# S2C_IOs3V3.net
KiCad netlist of a schematic drawn in Altium Designer
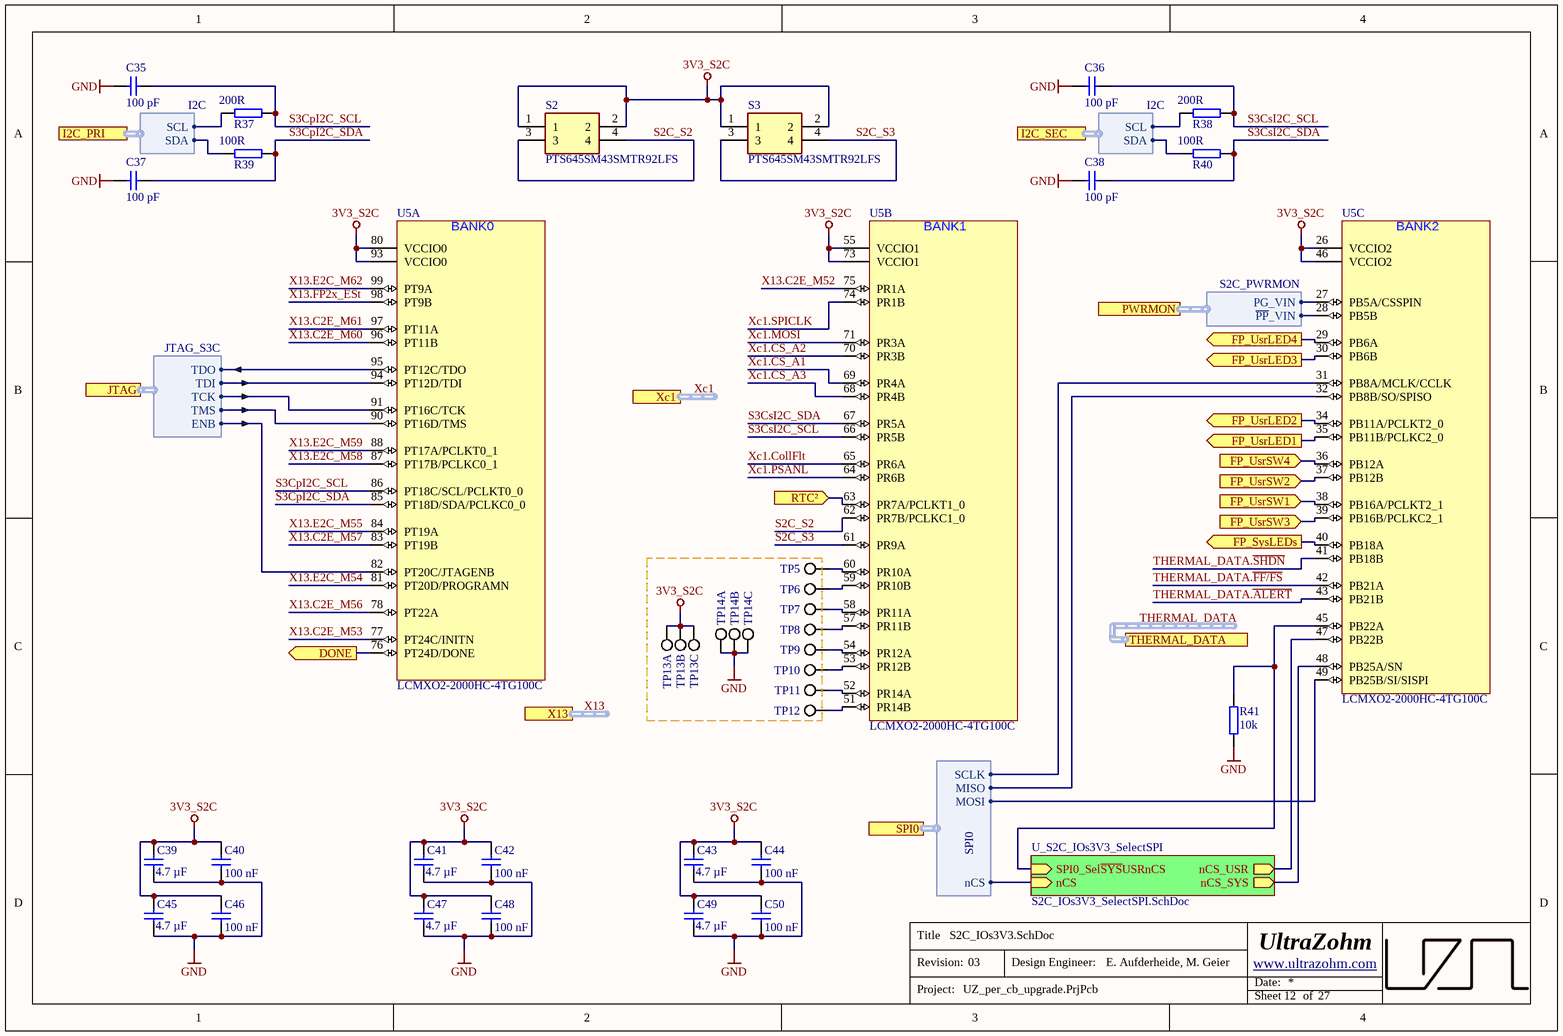
[diagram p0: S2C_IOs3V3.SchDoc]

(export (version "E")
  (design (tool "Eeschema 10.0.6"))
  (components
    (comp (ref "C35")
      (value "100 pF")
      (footprint "C_0603_TE")
      (description "Generic capacitor")
      (fields
        (field (name "MANUFACTURER PART NUMBER") "UZgen_C_0603_100pF_50V_X7R")
        (field (name "MANUFACTURER") "UZgen")
        (field (name "CREATED FROM") "UZgenTool")
      )
      (libsource (lib "user") (part "CAP-NP"))
    )
    (comp (ref "C36")
      (value "100 pF")
      (footprint "C_0603_TE")
      (description "Generic capacitor")
      (fields
        (field (name "MANUFACTURER PART NUMBER") "UZgen_C_0603_100pF_50V_X7R")
        (field (name "MANUFACTURER") "UZgen")
        (field (name "CREATED FROM") "UZgenTool")
      )
      (libsource (lib "user") (part "CAP-NP"))
    )
    (comp (ref "C37")
      (value "100 pF")
      (footprint "C_0603_TE")
      (description "Generic capacitor")
      (fields
        (field (name "MANUFACTURER PART NUMBER") "UZgen_C_0603_100pF_50V_X7R")
        (field (name "MANUFACTURER") "UZgen")
        (field (name "CREATED FROM") "UZgenTool")
      )
      (libsource (lib "user") (part "CAP-NP"))
    )
    (comp (ref "C38")
      (value "100 pF")
      (footprint "C_0603_TE")
      (description "Generic capacitor")
      (fields
        (field (name "MANUFACTURER PART NUMBER") "UZgen_C_0603_100pF_50V_X7R")
        (field (name "MANUFACTURER") "UZgen")
        (field (name "CREATED FROM") "UZgenTool")
      )
      (libsource (lib "user") (part "CAP-NP"))
    )
    (comp (ref "C39")
      (value "4.7 µF")
      (footprint "C_0603_TE")
      (description "Generic capacitor")
      (fields
        (field (name "MANUFACTURER PART NUMBER") "UZgen_C_0603_4.7uF_16V_X5R")
        (field (name "MANUFACTURER") "UZgen")
        (field (name "CREATED FROM") "MGeier")
      )
      (libsource (lib "user") (part "CAP-NP"))
    )
    (comp (ref "C40")
      (value "100 nF")
      (footprint "C_0603_TE")
      (description "Generic capacitor")
      (fields
        (field (name "TOLERANCE") "10 %")
        (field (name "VOLTAGE") "50 V")
        (field (name "CREATED FROM") "AGeiger")
      )
      (libsource (lib "user") (part "CAP-NP"))
    )
    (comp (ref "C41")
      (value "4.7 µF")
      (footprint "C_0603_TE")
      (description "Generic capacitor")
      (fields
        (field (name "MANUFACTURER PART NUMBER") "UZgen_C_0603_4.7uF_16V_X5R")
        (field (name "MANUFACTURER") "UZgen")
        (field (name "CREATED FROM") "MGeier")
      )
      (libsource (lib "user") (part "CAP-NP"))
    )
    (comp (ref "C42")
      (value "100 nF")
      (footprint "C_0603_TE")
      (description "Generic capacitor")
      (fields
        (field (name "TOLERANCE") "10 %")
        (field (name "VOLTAGE") "50 V")
        (field (name "CREATED FROM") "AGeiger")
      )
      (libsource (lib "user") (part "CAP-NP"))
    )
    (comp (ref "C43")
      (value "4.7 µF")
      (footprint "C_0603_TE")
      (description "Generic capacitor")
      (fields
        (field (name "MANUFACTURER PART NUMBER") "UZgen_C_0603_4.7uF_16V_X5R")
        (field (name "MANUFACTURER") "UZgen")
        (field (name "CREATED FROM") "MGeier")
      )
      (libsource (lib "user") (part "CAP-NP"))
    )
    (comp (ref "C44")
      (value "100 nF")
      (footprint "C_0603_TE")
      (description "Generic capacitor")
      (fields
        (field (name "TOLERANCE") "10 %")
        (field (name "VOLTAGE") "50 V")
        (field (name "CREATED FROM") "AGeiger")
      )
      (libsource (lib "user") (part "CAP-NP"))
    )
    (comp (ref "C45")
      (value "4.7 µF")
      (footprint "C_0603_TE")
      (description "Generic capacitor")
      (fields
        (field (name "MANUFACTURER PART NUMBER") "UZgen_C_0603_4.7uF_16V_X5R")
        (field (name "MANUFACTURER") "UZgen")
        (field (name "CREATED FROM") "MGeier")
      )
      (libsource (lib "user") (part "CAP-NP"))
    )
    (comp (ref "C46")
      (value "100 nF")
      (footprint "C_0603_TE")
      (description "Generic capacitor")
      (fields
        (field (name "TOLERANCE") "10 %")
        (field (name "VOLTAGE") "50 V")
        (field (name "CREATED FROM") "AGeiger")
      )
      (libsource (lib "user") (part "CAP-NP"))
    )
    (comp (ref "C47")
      (value "4.7 µF")
      (footprint "C_0603_TE")
      (description "Generic capacitor")
      (fields
        (field (name "MANUFACTURER PART NUMBER") "UZgen_C_0603_4.7uF_16V_X5R")
        (field (name "MANUFACTURER") "UZgen")
        (field (name "CREATED FROM") "MGeier")
      )
      (libsource (lib "user") (part "CAP-NP"))
    )
    (comp (ref "C48")
      (value "100 nF")
      (footprint "C_0603_TE")
      (description "Generic capacitor")
      (fields
        (field (name "TOLERANCE") "10 %")
        (field (name "VOLTAGE") "50 V")
        (field (name "CREATED FROM") "AGeiger")
      )
      (libsource (lib "user") (part "CAP-NP"))
    )
    (comp (ref "C49")
      (value "4.7 µF")
      (footprint "C_0603_TE")
      (description "Generic capacitor")
      (fields
        (field (name "MANUFACTURER PART NUMBER") "UZgen_C_0603_4.7uF_16V_X5R")
        (field (name "MANUFACTURER") "UZgen")
        (field (name "CREATED FROM") "MGeier")
      )
      (libsource (lib "user") (part "CAP-NP"))
    )
    (comp (ref "C50")
      (value "100 nF")
      (footprint "C_0603_TE")
      (description "Generic capacitor")
      (fields
        (field (name "TOLERANCE") "10 %")
        (field (name "VOLTAGE") "50 V")
        (field (name "CREATED FROM") "AGeiger")
      )
      (libsource (lib "user") (part "CAP-NP"))
    )
    (comp (ref "R37")
      (value "200R")
      (footprint "R_0603_TE")
      (description "Generic resistor")
      (fields
        (field (name "MANUFACTURER PART NUMBER") "UZgen_R_0603_200R")
        (field (name "MANUFACTURER") "UZgen")
        (field (name "CREATED FROM") "UZgenTool")
      )
      (libsource (lib "user") (part "RES"))
    )
    (comp (ref "R38")
      (value "200R")
      (footprint "R_0603_TE")
      (description "Generic resistor")
      (fields
        (field (name "MANUFACTURER PART NUMBER") "UZgen_R_0603_200R")
        (field (name "MANUFACTURER") "UZgen")
        (field (name "CREATED FROM") "UZgenTool")
      )
      (libsource (lib "user") (part "RES"))
    )
    (comp (ref "R39")
      (value "100R")
      (footprint "R_0603_TE")
      (description "Generic resistor")
      (fields
        (field (name "MANUFACTURER PART NUMBER") "UZgen_R_0603_100R")
        (field (name "MANUFACTURER") "UZgen")
        (field (name "CREATED FROM") "UZgenTool")
      )
      (libsource (lib "user") (part "RES"))
    )
    (comp (ref "R40")
      (value "100R")
      (footprint "R_0603_TE")
      (description "Generic resistor")
      (fields
        (field (name "MANUFACTURER PART NUMBER") "UZgen_R_0603_100R")
        (field (name "MANUFACTURER") "UZgen")
        (field (name "CREATED FROM") "UZgenTool")
      )
      (libsource (lib "user") (part "RES"))
    )
    (comp (ref "R41")
      (value "10k")
      (footprint "R_0603_TE")
      (description "Generic resistor")
      (fields
        (field (name "MANUFACTURER PART NUMBER") "UZgen_R_0603_10k")
        (field (name "MANUFACTURER") "UZgen")
        (field (name "CREATED FROM") "AGeiger")
      )
      (libsource (lib "user") (part "RES"))
    )
    (comp (ref "S2")
      (value "PTS645SM43SMTR92LFS")
      (footprint "PTS645_SMT")
      (description "50mA SPST 160gf 12V SMD-4P,6x6mm Tactile Switches ROHS")
      (fields
        (field (name "MOUSER PART NUMBER") "611-PTS645SM43SMTR92")
        (field (name "MANUFACTURER") "C&K COMPONENTS")
        (field (name "CREATED FROM") "AGeiger")
      )
      (libsource (lib "user") (part "PTS645SM43SMTR92LFS"))
    )
    (comp (ref "S3")
      (value "PTS645SM43SMTR92LFS")
      (footprint "PTS645_SMT")
      (description "50mA SPST 160gf 12V SMD-4P,6x6mm Tactile Switches ROHS")
      (fields
        (field (name "MOUSER PART NUMBER") "611-PTS645SM43SMTR92")
        (field (name "MANUFACTURER") "C&K COMPONENTS")
        (field (name "CREATED FROM") "AGeiger")
      )
      (libsource (lib "user") (part "PTS645SM43SMTR92LFS"))
    )
    (comp (ref "TP5")
      (value "PR10A")
      (footprint "FP-5015-MFG")
      (description "Circuit Board Hardware - PCB SM TEST POINT ON T&R - MINIATURE")
      (fields
        (field (name "MANUFACTURER PART NUMBER") "5015")
        (field (name "MANUFACTURER") "Keystone Electronics")
        (field (name "CREATED FROM") "AGeiger")
      )
      (libsource (lib "user") (part "SMD Testpoint"))
    )
    (comp (ref "TP6")
      (value "PR10B")
      (footprint "FP-5015-MFG")
      (description "Circuit Board Hardware - PCB SM TEST POINT ON T&R - MINIATURE")
      (fields
        (field (name "MANUFACTURER PART NUMBER") "5015")
        (field (name "MANUFACTURER") "Keystone Electronics")
        (field (name "CREATED FROM") "AGeiger")
      )
      (libsource (lib "user") (part "SMD Testpoint"))
    )
    (comp (ref "TP7")
      (value "PR11A")
      (footprint "FP-5015-MFG")
      (description "Circuit Board Hardware - PCB SM TEST POINT ON T&R - MINIATURE")
      (fields
        (field (name "MANUFACTURER PART NUMBER") "5015")
        (field (name "MANUFACTURER") "Keystone Electronics")
        (field (name "CREATED FROM") "AGeiger")
      )
      (libsource (lib "user") (part "SMD Testpoint"))
    )
    (comp (ref "TP8")
      (value "PR11B")
      (footprint "FP-5015-MFG")
      (description "Circuit Board Hardware - PCB SM TEST POINT ON T&R - MINIATURE")
      (fields
        (field (name "MANUFACTURER PART NUMBER") "5015")
        (field (name "MANUFACTURER") "Keystone Electronics")
        (field (name "CREATED FROM") "AGeiger")
      )
      (libsource (lib "user") (part "SMD Testpoint"))
    )
    (comp (ref "TP9")
      (value "PR12A")
      (footprint "FP-5015-MFG")
      (description "Circuit Board Hardware - PCB SM TEST POINT ON T&R - MINIATURE")
      (fields
        (field (name "MANUFACTURER PART NUMBER") "5015")
        (field (name "MANUFACTURER") "Keystone Electronics")
        (field (name "CREATED FROM") "AGeiger")
      )
      (libsource (lib "user") (part "SMD Testpoint"))
    )
    (comp (ref "TP10")
      (value "PR12B")
      (footprint "FP-5015-MFG")
      (description "Circuit Board Hardware - PCB SM TEST POINT ON T&R - MINIATURE")
      (fields
        (field (name "MANUFACTURER PART NUMBER") "5015")
        (field (name "MANUFACTURER") "Keystone Electronics")
        (field (name "CREATED FROM") "AGeiger")
      )
      (libsource (lib "user") (part "SMD Testpoint"))
    )
    (comp (ref "TP11")
      (value "PR14A")
      (footprint "FP-5015-MFG")
      (description "Circuit Board Hardware - PCB SM TEST POINT ON T&R - MINIATURE")
      (fields
        (field (name "MANUFACTURER PART NUMBER") "5015")
        (field (name "MANUFACTURER") "Keystone Electronics")
        (field (name "CREATED FROM") "AGeiger")
      )
      (libsource (lib "user") (part "SMD Testpoint"))
    )
    (comp (ref "TP12")
      (value "PR14B")
      (footprint "FP-5015-MFG")
      (description "Circuit Board Hardware - PCB SM TEST POINT ON T&R - MINIATURE")
      (fields
        (field (name "MANUFACTURER PART NUMBER") "5015")
        (field (name "MANUFACTURER") "Keystone Electronics")
        (field (name "CREATED FROM") "AGeiger")
      )
      (libsource (lib "user") (part "SMD Testpoint"))
    )
    (comp (ref "TP13A")
      (value "3V3_S2C")
      (footprint "FP-5015-MFG")
      (description "Circuit Board Hardware - PCB SM TEST POINT ON T&R - MINIATURE")
      (fields
        (field (name "MANUFACTURER PART NUMBER") "5015")
        (field (name "MANUFACTURER") "Keystone Electronics")
        (field (name "CREATED FROM") "AGeiger")
      )
      (libsource (lib "user") (part "SMD Testpoint"))
    )
    (comp (ref "TP13B")
      (value "3V3_S2C")
      (footprint "FP-5015-MFG")
      (description "Circuit Board Hardware - PCB SM TEST POINT ON T&R - MINIATURE")
      (fields
        (field (name "MANUFACTURER PART NUMBER") "5015")
        (field (name "MANUFACTURER") "Keystone Electronics")
        (field (name "CREATED FROM") "AGeiger")
      )
      (libsource (lib "user") (part "SMD Testpoint"))
    )
    (comp (ref "TP13C")
      (value "3V3_S2C")
      (footprint "FP-5015-MFG")
      (description "Circuit Board Hardware - PCB SM TEST POINT ON T&R - MINIATURE")
      (fields
        (field (name "MANUFACTURER PART NUMBER") "5015")
        (field (name "MANUFACTURER") "Keystone Electronics")
        (field (name "CREATED FROM") "AGeiger")
      )
      (libsource (lib "user") (part "SMD Testpoint"))
    )
    (comp (ref "TP14A")
      (value "GND")
      (footprint "FP-5015-MFG")
      (description "Circuit Board Hardware - PCB SM TEST POINT ON T&R - MINIATURE")
      (fields
        (field (name "MANUFACTURER PART NUMBER") "5015")
        (field (name "MANUFACTURER") "Keystone Electronics")
        (field (name "CREATED FROM") "AGeiger")
      )
      (libsource (lib "user") (part "SMD Testpoint"))
    )
    (comp (ref "TP14B")
      (value "GND")
      (footprint "FP-5015-MFG")
      (description "Circuit Board Hardware - PCB SM TEST POINT ON T&R - MINIATURE")
      (fields
        (field (name "MANUFACTURER PART NUMBER") "5015")
        (field (name "MANUFACTURER") "Keystone Electronics")
        (field (name "CREATED FROM") "AGeiger")
      )
      (libsource (lib "user") (part "SMD Testpoint"))
    )
    (comp (ref "TP14C")
      (value "GND")
      (footprint "FP-5015-MFG")
      (description "Circuit Board Hardware - PCB SM TEST POINT ON T&R - MINIATURE")
      (fields
        (field (name "MANUFACTURER PART NUMBER") "5015")
        (field (name "MANUFACTURER") "Keystone Electronics")
        (field (name "CREATED FROM") "AGeiger")
      )
      (libsource (lib "user") (part "SMD Testpoint"))
    )
    (comp (ref "U5")
      (value "LCMXO2-2000HC-4TG100C")
      (footprint "QFP50P1600X1600X160-100N")
      (description "TQFP-100(14x14) Programmable Logic Device (CPLDs/FPGAs) ROHS")
      (fields
        (field (name "MANUFACTURER") "Lattice")
        (field (name "LCSC PART NUMBER") "C1521632")
        (field (name "CREATED FROM") "FRosner")
      )
      (libsource (lib "user") (part "LCMXO2-2000"))
    )
  )
  (nets
    (net (code "8") (name "/DONE") (class "Default")
      (node (ref "U5") (pin "76") (pinfunction "PT24D/DONE_76") (pintype "bidirectional"))
    )
    (net (code "9") (name "/ENB") (class "Default")
      (node (ref "U5") (pin "82") (pinfunction "PT20C/JTAGENB_82") (pintype "bidirectional"))
    )
    (net (code "10") (name "/FP_SysLEDs") (class "Default")
      (node (ref "U5") (pin "40") (pinfunction "PB18A_40") (pintype "bidirectional"))
    )
    (net (code "11") (name "/FP_UsrLED1") (class "Default")
      (node (ref "U5") (pin "35") (pinfunction "PB11B/PCLKC2_0_35") (pintype "bidirectional"))
    )
    (net (code "12") (name "/FP_UsrLED2") (class "Default")
      (node (ref "U5") (pin "34") (pinfunction "PB11A/PCLKT2_0_34") (pintype "bidirectional"))
    )
    (net (code "13") (name "/FP_UsrLED3") (class "Default")
      (node (ref "U5") (pin "30") (pinfunction "PB6B_30") (pintype "bidirectional"))
    )
    (net (code "14") (name "/FP_UsrLED4") (class "Default")
      (node (ref "U5") (pin "29") (pinfunction "PB6A_29") (pintype "bidirectional"))
    )
    (net (code "15") (name "/FP_UsrSW1") (class "Default")
      (node (ref "U5") (pin "38") (pinfunction "PB16A/PCLKT2_1_38") (pintype "bidirectional"))
    )
    (net (code "16") (name "/FP_UsrSW2") (class "Default")
      (node (ref "U5") (pin "37") (pinfunction "PB12B_37") (pintype "bidirectional"))
    )
    (net (code "17") (name "/FP_UsrSW3") (class "Default")
      (node (ref "U5") (pin "39") (pinfunction "PB16B/PCLKC2_1_39") (pintype "bidirectional"))
    )
    (net (code "18") (name "/FP_UsrSW4") (class "Default")
      (node (ref "U5") (pin "36") (pinfunction "PB12A_36") (pintype "bidirectional"))
    )
    (net (code "19") (name "/MISO") (class "Default")
      (node (ref "U5") (pin "32") (pinfunction "PB8B/SO/SPISO_32") (pintype "bidirectional"))
    )
    (net (code "20") (name "/MOSI") (class "Default")
      (node (ref "U5") (pin "49") (pinfunction "PB25B/SI/SISPI_49") (pintype "bidirectional"))
    )
    (net (code "21") (name "/PG_VIN") (class "Default")
      (node (ref "U5") (pin "27") (pinfunction "PB5A/CSSPIN_27") (pintype "bidirectional"))
    )
    (net (code "22") (name "/RTC²") (class "Default")
      (node (ref "U5") (pin "63") (pinfunction "PR7A/PCLKT1_0_63") (pintype "bidirectional"))
    )
    (net (code "23") (name "/S2C_S2") (class "Default")
      (node (ref "S2") (pin "3") (pinfunction "3_3") (pintype "passive"))
      (node (ref "S2") (pin "4") (pinfunction "4_4") (pintype "passive"))
      (node (ref "U5") (pin "62") (pinfunction "PR7B/PCLKC1_0_62") (pintype "bidirectional"))
    )
    (net (code "24") (name "/S2C_S3") (class "Default")
      (node (ref "S3") (pin "3") (pinfunction "3_3") (pintype "passive"))
      (node (ref "S3") (pin "4") (pinfunction "4_4") (pintype "passive"))
      (node (ref "U5") (pin "61") (pinfunction "PR9A_61") (pintype "bidirectional"))
    )
    (net (code "25") (name "/S3CpI2C_SCL") (class "Default")
      (node (ref "C35") (pin "1") (pinfunction "1_1") (pintype "passive"))
      (node (ref "R37") (pin "2") (pinfunction "2_2") (pintype "passive"))
      (node (ref "U5") (pin "86") (pinfunction "PT18C/SCL/PCLKT0_0_86") (pintype "bidirectional"))
    )
    (net (code "26") (name "/S3CpI2C_SDA") (class "Default")
      (node (ref "C37") (pin "1") (pinfunction "1_1") (pintype "passive"))
      (node (ref "R39") (pin "2") (pinfunction "2_2") (pintype "passive"))
      (node (ref "U5") (pin "85") (pinfunction "PT18D/SDA/PCLKC0_0_85") (pintype "bidirectional"))
    )
    (net (code "27") (name "/S3CsI2C_SCL") (class "Default")
      (node (ref "C36") (pin "1") (pinfunction "1_1") (pintype "passive"))
      (node (ref "R38") (pin "2") (pinfunction "2_2") (pintype "passive"))
      (node (ref "U5") (pin "66") (pinfunction "PR5B_66") (pintype "bidirectional"))
    )
    (net (code "28") (name "/S3CsI2C_SDA") (class "Default")
      (node (ref "C38") (pin "1") (pinfunction "1_1") (pintype "passive"))
      (node (ref "R40") (pin "2") (pinfunction "2_2") (pintype "passive"))
      (node (ref "U5") (pin "67") (pinfunction "PR5A_67") (pintype "bidirectional"))
    )
    (net (code "29") (name "/SCLK") (class "Default")
      (node (ref "U5") (pin "31") (pinfunction "PB8A/MCLK/CCLK_31") (pintype "bidirectional"))
    )
    (net (code "30") (name "/SPI0_Sel~{SYS}USRnCS") (class "Default")
      (node (ref "R41") (pin "2") (pinfunction "2_2") (pintype "passive"))
      (node (ref "U5") (pin "45") (pinfunction "PB22A_45") (pintype "bidirectional"))
    )
    (net (code "31") (name "/TCK") (class "Default")
      (node (ref "U5") (pin "91") (pinfunction "PT16C/TCK_91") (pintype "bidirectional"))
    )
    (net (code "32") (name "/TDI") (class "Default")
      (node (ref "U5") (pin "94") (pinfunction "PT12D/TDI_94") (pintype "bidirectional"))
    )
    (net (code "33") (name "/TDO") (class "Default")
      (node (ref "U5") (pin "95") (pinfunction "PT12C/TDO_95") (pintype "bidirectional"))
    )
    (net (code "34") (name "/THERMAL_DATA.~{ALERT}") (class "Default")
      (node (ref "U5") (pin "43") (pinfunction "PB21B_43") (pintype "bidirectional"))
    )
    (net (code "35") (name "/THERMAL_DATA.~{FF{slash}FS}") (class "Default")
      (node (ref "U5") (pin "42") (pinfunction "PB21A_42") (pintype "bidirectional"))
    )
    (net (code "36") (name "/THERMAL_DATA.~{SHDN}") (class "Default")
      (node (ref "U5") (pin "41") (pinfunction "PB18B_41") (pintype "bidirectional"))
    )
    (net (code "37") (name "/TMS") (class "Default")
      (node (ref "U5") (pin "90") (pinfunction "PT16D/TMS_90") (pintype "bidirectional"))
    )
    (net (code "38") (name "/X13.C2E_M52") (class "Default")
      (node (ref "U5") (pin "75") (pinfunction "PR1A_75") (pintype "bidirectional"))
    )
    (net (code "39") (name "/X13.C2E_M53") (class "Default")
      (node (ref "U5") (pin "77") (pinfunction "PT24C/INITN_77") (pintype "bidirectional"))
    )
    (net (code "40") (name "/X13.C2E_M56") (class "Default")
      (node (ref "U5") (pin "78") (pinfunction "PT22A_78") (pintype "bidirectional"))
    )
    (net (code "41") (name "/X13.C2E_M57") (class "Default")
      (node (ref "U5") (pin "83") (pinfunction "PT19B_83") (pintype "bidirectional"))
    )
    (net (code "42") (name "/X13.C2E_M60") (class "Default")
      (node (ref "U5") (pin "96") (pinfunction "PT11B_96") (pintype "bidirectional"))
    )
    (net (code "43") (name "/X13.C2E_M61") (class "Default")
      (node (ref "U5") (pin "97") (pinfunction "PT11A_97") (pintype "bidirectional"))
    )
    (net (code "44") (name "/X13.E2C_M54") (class "Default")
      (node (ref "U5") (pin "81") (pinfunction "PT20D/PROGRAMN_81") (pintype "bidirectional"))
    )
    (net (code "45") (name "/X13.E2C_M55") (class "Default")
      (node (ref "U5") (pin "84") (pinfunction "PT19A_84") (pintype "bidirectional"))
    )
    (net (code "46") (name "/X13.E2C_M58") (class "Default")
      (node (ref "U5") (pin "87") (pinfunction "PT17B/PCLKC0_1_87") (pintype "bidirectional"))
    )
    (net (code "47") (name "/X13.E2C_M59") (class "Default")
      (node (ref "U5") (pin "88") (pinfunction "PT17A/PCLKT0_1_88") (pintype "bidirectional"))
    )
    (net (code "48") (name "/X13.E2C_M62") (class "Default")
      (node (ref "U5") (pin "99") (pinfunction "PT9A_99") (pintype "bidirectional"))
    )
    (net (code "49") (name "/X13.FP2x_ESt") (class "Default")
      (node (ref "U5") (pin "98") (pinfunction "PT9B_98") (pintype "bidirectional"))
    )
    (net (code "50") (name "/Xc1.CS_A1") (class "Default")
      (node (ref "U5") (pin "69") (pinfunction "PR4A_69") (pintype "bidirectional"))
    )
    (net (code "51") (name "/Xc1.CS_A2") (class "Default")
      (node (ref "U5") (pin "70") (pinfunction "PR3B_70") (pintype "bidirectional"))
    )
    (net (code "52") (name "/Xc1.CS_A3") (class "Default")
      (node (ref "U5") (pin "68") (pinfunction "PR4B_68") (pintype "bidirectional"))
    )
    (net (code "53") (name "/Xc1.CollFlt") (class "Default")
      (node (ref "U5") (pin "65") (pinfunction "PR6A_65") (pintype "bidirectional"))
    )
    (net (code "54") (name "/Xc1.MOSI") (class "Default")
      (node (ref "U5") (pin "71") (pinfunction "PR3A_71") (pintype "bidirectional"))
    )
    (net (code "55") (name "/Xc1.PSANL") (class "Default")
      (node (ref "U5") (pin "64") (pinfunction "PR6B_64") (pintype "bidirectional"))
    )
    (net (code "56") (name "/Xc1.SPICLK") (class "Default")
      (node (ref "U5") (pin "74") (pinfunction "PR1B_74") (pintype "bidirectional"))
    )
    (net (code "58") (name "/nCS_SYS") (class "Default")
      (node (ref "U5") (pin "48") (pinfunction "PB25A/SN_48") (pintype "bidirectional"))
    )
    (net (code "59") (name "/nCS_USR") (class "Default")
      (node (ref "U5") (pin "47") (pinfunction "PB22B_47") (pintype "bidirectional"))
    )
    (net (code "67") (name "/~{PP}_VIN") (class "Default")
      (node (ref "U5") (pin "28") (pinfunction "PB5B_28") (pintype "bidirectional"))
    )
    (net (code "68") (name "3V3_S2C") (class "Default")
      (node (ref "C39") (pin "1") (pinfunction "1_1") (pintype "passive"))
      (node (ref "C40") (pin "2") (pinfunction "2_2") (pintype "passive"))
      (node (ref "C41") (pin "1") (pinfunction "1_1") (pintype "passive"))
      (node (ref "C42") (pin "2") (pinfunction "2_2") (pintype "passive"))
      (node (ref "C43") (pin "1") (pinfunction "1_1") (pintype "passive"))
      (node (ref "C44") (pin "2") (pinfunction "2_2") (pintype "passive"))
      (node (ref "C45") (pin "1") (pinfunction "1_1") (pintype "passive"))
      (node (ref "C46") (pin "2") (pinfunction "2_2") (pintype "passive"))
      (node (ref "C47") (pin "1") (pinfunction "1_1") (pintype "passive"))
      (node (ref "C48") (pin "2") (pinfunction "2_2") (pintype "passive"))
      (node (ref "C49") (pin "1") (pinfunction "1_1") (pintype "passive"))
      (node (ref "C50") (pin "2") (pinfunction "2_2") (pintype "passive"))
      (node (ref "S2") (pin "1") (pinfunction "1_1") (pintype "passive"))
      (node (ref "S2") (pin "2") (pinfunction "2_2") (pintype "passive"))
      (node (ref "S3") (pin "1") (pinfunction "1_1") (pintype "passive"))
      (node (ref "S3") (pin "2") (pinfunction "2_2") (pintype "passive"))
      (node (ref "TP13A") (pin "1") (pinfunction "1_1") (pintype "passive"))
      (node (ref "TP13B") (pin "1") (pinfunction "1_1") (pintype "passive"))
      (node (ref "TP13C") (pin "1") (pinfunction "1_1") (pintype "passive"))
      (node (ref "U5") (pin "26") (pinfunction "VCCIO2_26") (pintype "power_in"))
      (node (ref "U5") (pin "46") (pinfunction "VCCIO2_46") (pintype "power_in"))
      (node (ref "U5") (pin "55") (pinfunction "VCCIO1_55") (pintype "power_in"))
      (node (ref "U5") (pin "73") (pinfunction "VCCIO1_73") (pintype "power_in"))
      (node (ref "U5") (pin "80") (pinfunction "VCCIO0_80") (pintype "power_in"))
      (node (ref "U5") (pin "93") (pinfunction "VCCIO0_93") (pintype "power_in"))
    )
    (net (code "69") (name "GND") (class "Default")
      (node (ref "C35") (pin "2") (pinfunction "2_2") (pintype "passive"))
      (node (ref "C36") (pin "2") (pinfunction "2_2") (pintype "passive"))
      (node (ref "C37") (pin "2") (pinfunction "2_2") (pintype "passive"))
      (node (ref "C38") (pin "2") (pinfunction "2_2") (pintype "passive"))
      (node (ref "C39") (pin "2") (pinfunction "2_2") (pintype "passive"))
      (node (ref "C40") (pin "1") (pinfunction "1_1") (pintype "passive"))
      (node (ref "C41") (pin "2") (pinfunction "2_2") (pintype "passive"))
      (node (ref "C42") (pin "1") (pinfunction "1_1") (pintype "passive"))
      (node (ref "C43") (pin "2") (pinfunction "2_2") (pintype "passive"))
      (node (ref "C44") (pin "1") (pinfunction "1_1") (pintype "passive"))
      (node (ref "C45") (pin "2") (pinfunction "2_2") (pintype "passive"))
      (node (ref "C46") (pin "1") (pinfunction "1_1") (pintype "passive"))
      (node (ref "C47") (pin "2") (pinfunction "2_2") (pintype "passive"))
      (node (ref "C48") (pin "1") (pinfunction "1_1") (pintype "passive"))
      (node (ref "C49") (pin "2") (pinfunction "2_2") (pintype "passive"))
      (node (ref "C50") (pin "1") (pinfunction "1_1") (pintype "passive"))
      (node (ref "R41") (pin "1") (pinfunction "1_1") (pintype "passive"))
      (node (ref "TP14A") (pin "1") (pinfunction "1_1") (pintype "passive"))
      (node (ref "TP14B") (pin "1") (pinfunction "1_1") (pintype "passive"))
      (node (ref "TP14C") (pin "1") (pinfunction "1_1") (pintype "passive"))
    )
    (net (code "70") (name "Net-(U5B-PR10A)") (class "Default")
      (node (ref "TP5") (pin "1") (pinfunction "1_1") (pintype "passive"))
      (node (ref "U5") (pin "60") (pinfunction "PR10A_60") (pintype "bidirectional"))
    )
    (net (code "71") (name "Net-(U5B-PR10B)") (class "Default")
      (node (ref "TP6") (pin "1") (pinfunction "1_1") (pintype "passive"))
      (node (ref "U5") (pin "59") (pinfunction "PR10B_59") (pintype "bidirectional"))
    )
    (net (code "72") (name "Net-(U5B-PR11A)") (class "Default")
      (node (ref "TP7") (pin "1") (pinfunction "1_1") (pintype "passive"))
      (node (ref "U5") (pin "58") (pinfunction "PR11A_58") (pintype "bidirectional"))
    )
    (net (code "73") (name "Net-(U5B-PR11B)") (class "Default")
      (node (ref "TP8") (pin "1") (pinfunction "1_1") (pintype "passive"))
      (node (ref "U5") (pin "57") (pinfunction "PR11B_57") (pintype "bidirectional"))
    )
    (net (code "74") (name "Net-(U5B-PR12A)") (class "Default")
      (node (ref "TP9") (pin "1") (pinfunction "1_1") (pintype "passive"))
      (node (ref "U5") (pin "54") (pinfunction "PR12A_54") (pintype "bidirectional"))
    )
    (net (code "75") (name "Net-(U5B-PR12B)") (class "Default")
      (node (ref "TP10") (pin "1") (pinfunction "1_1") (pintype "passive"))
      (node (ref "U5") (pin "53") (pinfunction "PR12B_53") (pintype "bidirectional"))
    )
    (net (code "76") (name "Net-(U5B-PR14A)") (class "Default")
      (node (ref "TP11") (pin "1") (pinfunction "1_1") (pintype "passive"))
      (node (ref "U5") (pin "52") (pinfunction "PR14A_52") (pintype "bidirectional"))
    )
    (net (code "77") (name "Net-(U5B-PR14B)") (class "Default")
      (node (ref "TP12") (pin "1") (pinfunction "1_1") (pintype "passive"))
      (node (ref "U5") (pin "51") (pinfunction "PR14B_51") (pintype "bidirectional"))
    )
    (net (code "78") (name "unconnected-(R37-Pad1)") (class "Default")
      (node (ref "R37") (pin "1") (pinfunction "1_1") (pintype "passive"))
    )
    (net (code "79") (name "unconnected-(R38-Pad1)") (class "Default")
      (node (ref "R38") (pin "1") (pinfunction "1_1") (pintype "passive"))
    )
    (net (code "80") (name "unconnected-(R39-Pad1)") (class "Default")
      (node (ref "R39") (pin "1") (pinfunction "1_1") (pintype "passive"))
    )
    (net (code "81") (name "unconnected-(R40-Pad1)") (class "Default")
      (node (ref "R40") (pin "1") (pinfunction "1_1") (pintype "passive"))
    )
  )
)
